# 03_CPU01.net
KiCad netlist of a schematic drawn in Altium Designer
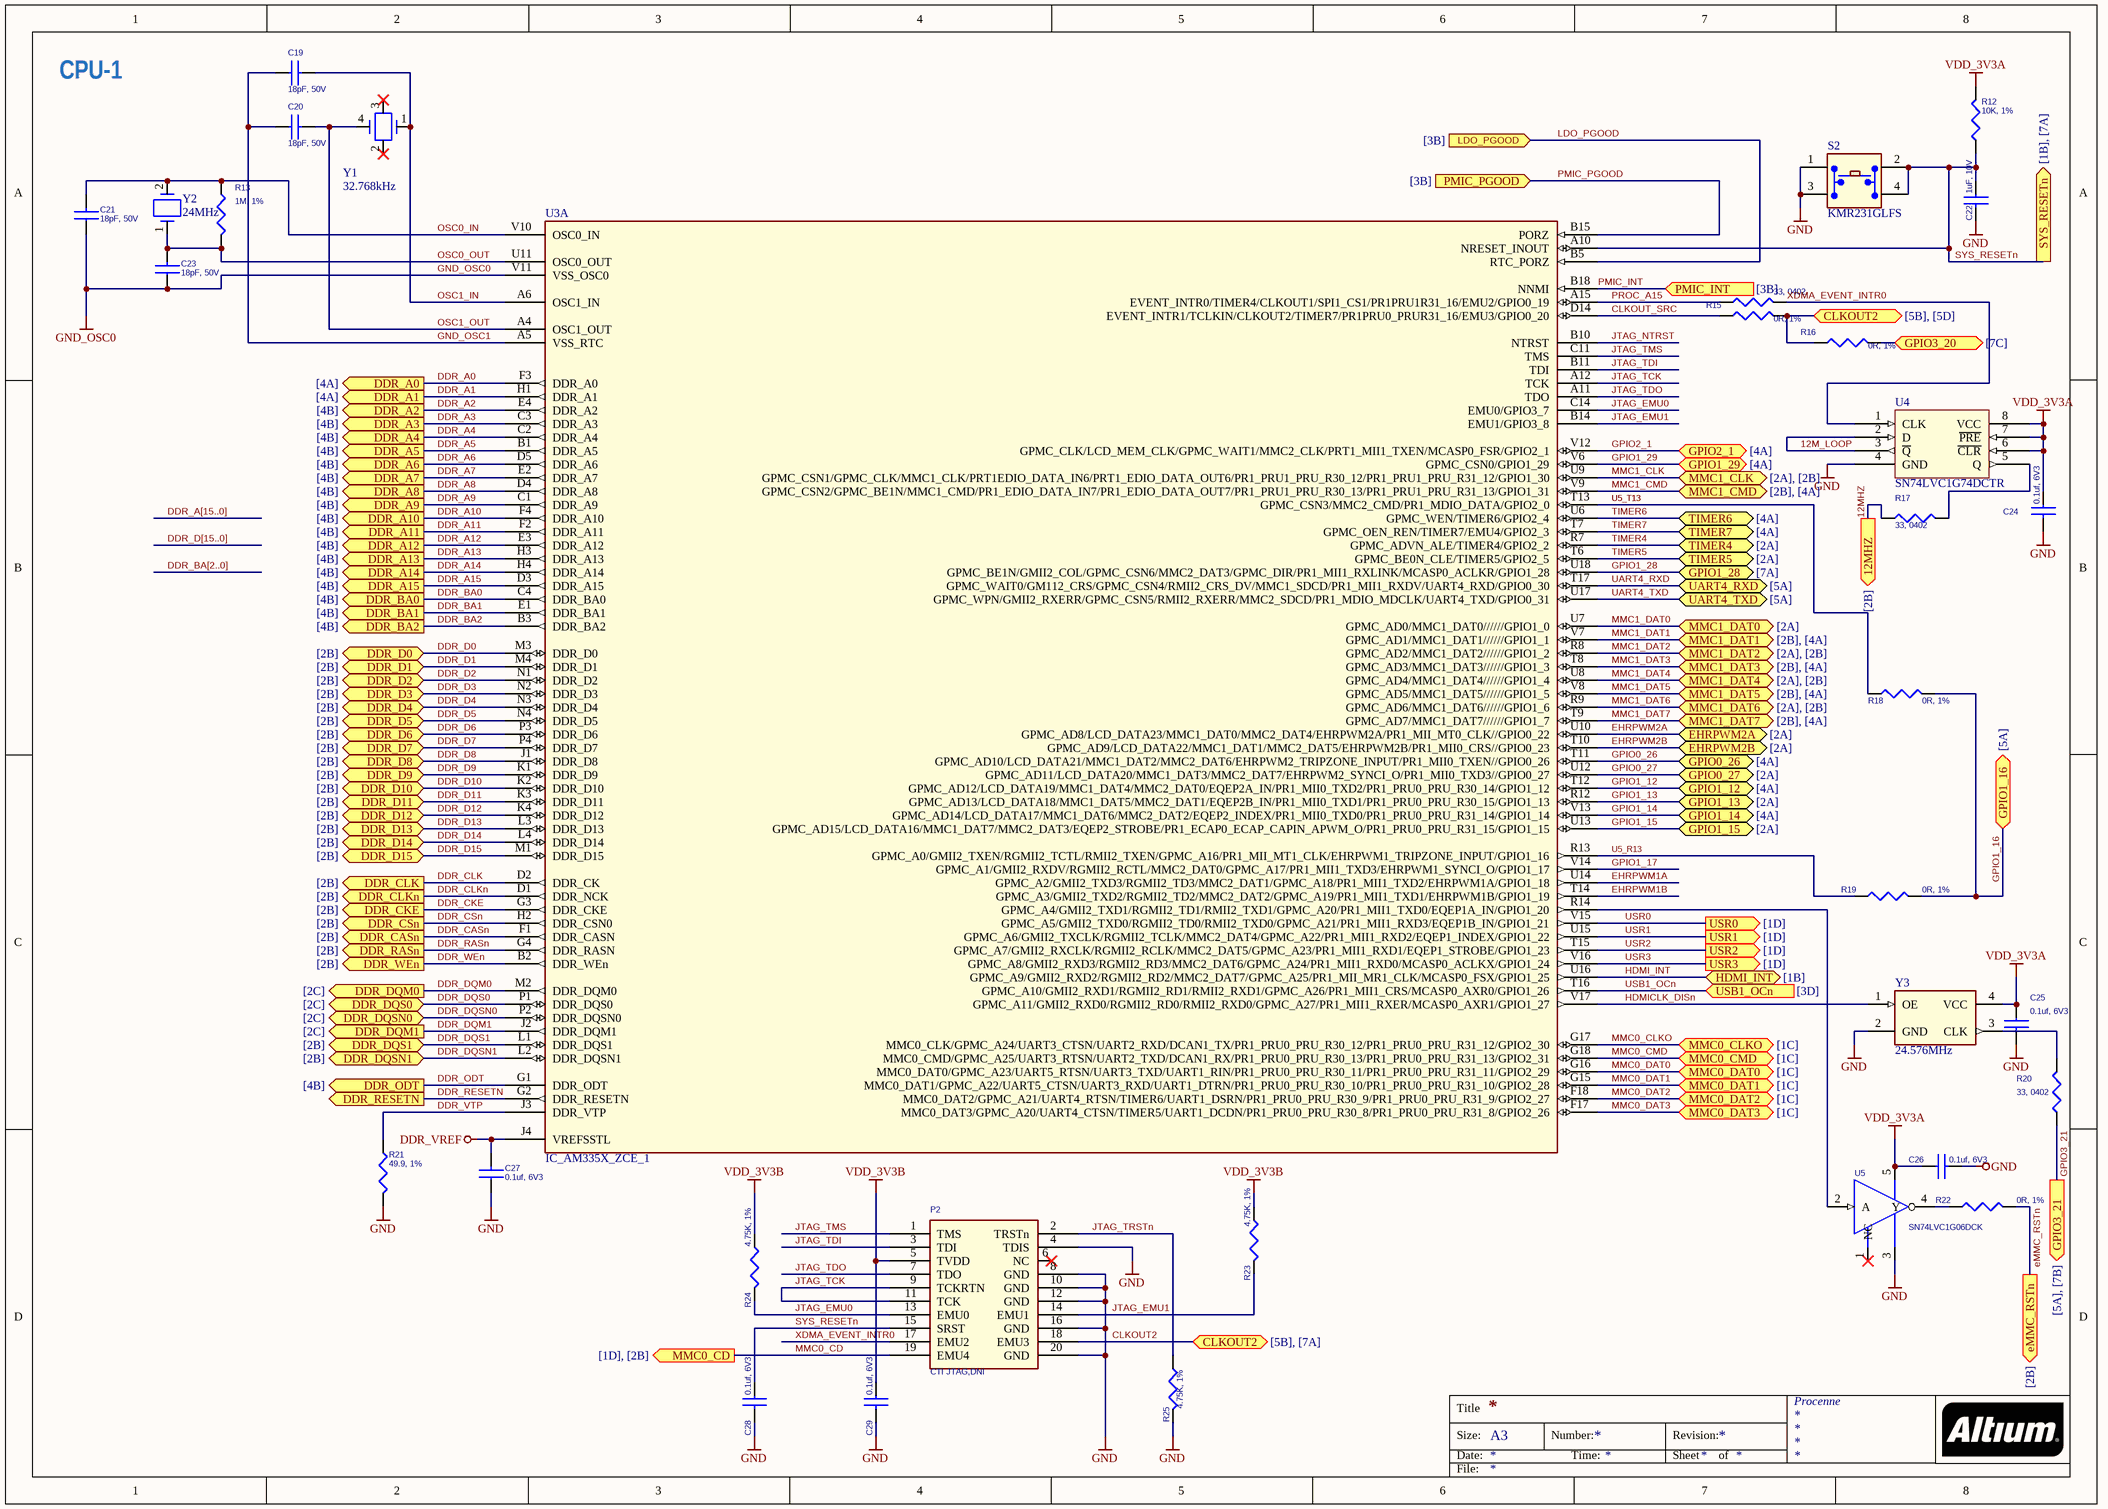
[diagram p0: 03_CPU01.SchDoc]

(export (version "E")
  (design (tool "Eeschema 10.0.6"))
  (components
    (comp (ref "C19")
      (value "18pF, 50V")
      (footprint "402")
      (description "CAP CER 18PF 50V 5% NP0 0402")
      (fields
        (field (name "MANUFACTURER") "TDK Corporation")
        (field (name "MANUFACTURER PART NUMBER") "C1005C0G1H180J050BA")
      )
      (libsource (lib "BEAGLEBONEBLACK_REV A5B") (part "CAP_18PF_COG_50V_5%_0402"))
    )
    (comp (ref "C20")
      (value "18pF, 50V")
      (footprint "402")
      (description "CAP CER 18PF 50V 5% NP0 0402")
      (fields
        (field (name "MANUFACTURER") "TDK Corporation")
        (field (name "MANUFACTURER PART NUMBER") "C1005C0G1H180J050BA")
      )
      (libsource (lib "BEAGLEBONEBLACK_REV A5B") (part "CAP_18PF_COG_50V_5%_0402"))
    )
    (comp (ref "C21")
      (value "18pF, 50V")
      (footprint "402")
      (description "CAP CER 18PF 50V 5% NP0 0402")
      (fields
        (field (name "MANUFACTURER") "TDK Corporation")
        (field (name "MANUFACTURER PART NUMBER") "C1005C0G1H180J050BA")
      )
      (libsource (lib "BEAGLEBONEBLACK_REV A5B_1") (part "CAP_18PF_COG_50V_5%_0402"))
    )
    (comp (ref "C22")
      (value "1uF, 10V")
      (footprint "402")
      (description "CAP CER 1UF 10V 10% X5R 0402")
      (fields
        (field (name "MANUFACTURER") "AVX Corporation")
        (field (name "MANUFACTURER PART NUMBER") "0402ZD105KAT2A")
      )
      (libsource (lib "BEAGLEBONEBLACK_REV A5B") (part "CAP_1.0UF_X5R_10V_10%_0402"))
    )
    (comp (ref "C23")
      (value "18pF, 50V")
      (footprint "402")
      (description "CAP CER 18PF 50V 5% NP0 0402")
      (fields
        (field (name "MANUFACTURER") "TDK Corporation")
        (field (name "MANUFACTURER PART NUMBER") "C1005C0G1H180J050BA")
      )
      (libsource (lib "BEAGLEBONEBLACK_REV A5B_1") (part "CAP_18PF_COG_50V_5%_0402"))
    )
    (comp (ref "C24")
      (value "0.1uf, 6V3")
      (footprint "402")
      (description "CAP CER 0.1UF 6.3V 10% X5R 0402")
      (fields
        (field (name "MANUFACTURER") "TDK Corporation")
        (field (name "MANUFACTURER PART NUMBER") "C1005X5R0J104K050BA")
      )
      (libsource (lib "BEAGLEBONEBLACK_REV A5B") (part "CAP_0.1uF_X7R_16V_10% 0402"))
    )
    (comp (ref "C25")
      (value "0.1uf, 6V3")
      (footprint "402")
      (description "CAP CER 0.1UF 6.3V 10% X5R 0402")
      (fields
        (field (name "MANUFACTURER") "TDK Corporation")
        (field (name "MANUFACTURER PART NUMBER") "C1005X5R0J104K050BA")
      )
      (libsource (lib "BEAGLEBONEBLACK_REV A5B") (part "CAP_0.1uF_X7R_16V_10% 0402"))
    )
    (comp (ref "C26")
      (value "0.1uf, 6V3")
      (footprint "402")
      (description "CAP CER 0.1UF 6.3V 10% X5R 0402")
      (fields
        (field (name "MANUFACTURER") "TDK Corporation")
        (field (name "MANUFACTURER PART NUMBER") "C1005X5R0J104K050BA")
      )
      (libsource (lib "BEAGLEBONEBLACK_REV A5B") (part "CAP_0.1uF_X7R_16V_10% 0402"))
    )
    (comp (ref "C27")
      (value "0.1uf, 6V3")
      (footprint "402")
      (description "CAP CER 0.1UF 6.3V 10% X5R 0402")
      (fields
        (field (name "MANUFACTURER") "TDK Corporation")
        (field (name "MANUFACTURER PART NUMBER") "C1005X5R0J104K050BA")
      )
      (libsource (lib "BEAGLEBONEBLACK_REV A5B_1") (part "CAP_0.1uF_X7R_16V_10% 0402"))
    )
    (comp (ref "C28")
      (value "0.1uf, 6V3")
      (footprint "402")
      (description "CAP CER 0.1UF 6.3V 10% X5R 0402")
      (fields
        (field (name "MANUFACTURER") "TDK Corporation")
        (field (name "MANUFACTURER PART NUMBER") "C1005X5R0J104K050BA")
      )
      (libsource (lib "BEAGLEBONEBLACK_REV A5B") (part "CAP_0.1uF_X7R_16V_10% 0402"))
    )
    (comp (ref "C29")
      (value "0.1uf, 6V3")
      (footprint "402")
      (description "CAP CER 0.1UF 6.3V 10% X5R 0402")
      (fields
        (field (name "MANUFACTURER") "TDK Corporation")
        (field (name "MANUFACTURER PART NUMBER") "C1005X5R0J104K050BA")
      )
      (libsource (lib "BEAGLEBONEBLACK_REV A5B") (part "CAP_0.1uF_X7R_16V_10% 0402"))
    )
    (comp (ref "P2")
      (value "CTI JTAG,DNI")
      (description "Dual Line Header 10x2pin Tin")
      (fields
        (field (name "MANUFACTURER") "Samtec Inc")
        (field (name "MANUFACTURER PART NUMBER") "FTR-110-03-G-D-06")
      )
      (libsource (lib "BEAGLEBONEBLACK_REV A5B") (part "HDR_10x2_CJTAG"))
    )
    (comp (ref "R12")
      (value "10K, 1%")
      (footprint "402")
      (description "RES 10K OHM 1/16W 5% 0402 SMD")
      (fields
        (field (name "MANUFACTURER") "Rohm Semiconductor")
        (field (name "MANUFACTURER PART NUMBER") "MCR01MZPJ103")
      )
      (libsource (lib "BEAGLEBONEBLACK_REV A5B_1") (part "RES_10K_1/16W_1%_0402"))
    )
    (comp (ref "R13")
      (value "1M, 1%")
      (footprint "402")
      (description "Resistor 1Mohm 1/16W 1% 0402")
      (fields
        (field (name "MANUFACTURER") "Stackpole Electronics Inc")
        (field (name "MANUFACTURER PART NUMBER") "RMCF0402FT1M00")
      )
      (libsource (lib "BEAGLEBONEBLACK_REV A5B_1") (part "RES_1M_1/16W_1%_0402"))
    )
    (comp (ref "R14")
      (value "33, 0402")
      (footprint "402")
      (description "RES 33 OHM 1/16W 5% 0402 SMD")
      (fields
        (field (name "MANUFACTURER") "Panasonic Electronic Components")
        (field (name "MANUFACTURER PART NUMBER") "ERJ-2GEJ330X")
      )
      (libsource (lib "BEAGLEBONEBLACK_REV A5B") (part "RES_33_0402"))
    )
    (comp (ref "R15")
      (value "0R, 1%")
      (footprint "402")
      (description "RES 0.0 OHM 1/16W 0402 SMD")
      (fields
        (field (name "MANUFACTURER") "Yageo")
        (field (name "MANUFACTURER PART NUMBER") "RC0402JR-070RL")
      )
      (libsource (lib "BEAGLEBONEBLACK_REV A5B") (part "RES_0_1/16W_1%_0402"))
    )
    (comp (ref "R16")
      (value "0R, 1%")
      (footprint "402")
      (description "RES 0.0 OHM 1/16W 0402 SMD")
      (fields
        (field (name "MANUFACTURER") "Yageo")
        (field (name "MANUFACTURER PART NUMBER") "RC0402JR-070RL")
      )
      (libsource (lib "BEAGLEBONEBLACK_REV A5B") (part "RES_0_1/16W_1%_0402"))
    )
    (comp (ref "R17")
      (value "33, 0402")
      (footprint "402")
      (description "RES 33 OHM 1/16W 5% 0402 SMD")
      (fields
        (field (name "MANUFACTURER") "Panasonic Electronic Components")
        (field (name "MANUFACTURER PART NUMBER") "ERJ-2GEJ330X")
      )
      (libsource (lib "BEAGLEBONEBLACK_REV A5B") (part "RES_33_0402"))
    )
    (comp (ref "R18")
      (value "0R, 1%")
      (footprint "402")
      (description "RES 0.0 OHM 1/16W 0402 SMD")
      (fields
        (field (name "MANUFACTURER") "Yageo")
        (field (name "MANUFACTURER PART NUMBER") "RC0402JR-070RL")
      )
      (libsource (lib "BEAGLEBONEBLACK_REV A5B") (part "RES_0_1/16W_1%_0402"))
    )
    (comp (ref "R19")
      (value "0R, 1%")
      (footprint "402")
      (description "RES 0.0 OHM 1/16W 0402 SMD")
      (fields
        (field (name "MANUFACTURER") "Yageo")
        (field (name "MANUFACTURER PART NUMBER") "RC0402JR-070RL")
      )
      (libsource (lib "BEAGLEBONEBLACK_REV A5B") (part "RES_0_1/16W_1%_0402"))
    )
    (comp (ref "R20")
      (value "33, 0402")
      (footprint "402")
      (description "RES 33 OHM 1/16W 5% 0402 SMD")
      (fields
        (field (name "MANUFACTURER") "Panasonic Electronic Components")
        (field (name "MANUFACTURER PART NUMBER") "ERJ-2GEJ330X")
      )
      (libsource (lib "BEAGLEBONEBLACK_REV A5B") (part "RES_33_0402"))
    )
    (comp (ref "R21")
      (value "49.9, 1%")
      (footprint "402")
      (description "RES 49.9 OHM 1/16W 1% 0402 SMD")
      (fields
        (field (name "MANUFACTURER") "Yageo")
        (field (name "MANUFACTURER PART NUMBER") "RC0402FR-0749R9L")
      )
      (libsource (lib "BEAGLEBONEBLACK_REV A5B_1") (part "RES_4.7K_0402"))
    )
    (comp (ref "R22")
      (value "0R, 1%")
      (footprint "402")
      (description "RES 0.0 OHM 1/16W 0402 SMD")
      (fields
        (field (name "MANUFACTURER") "Yageo")
        (field (name "MANUFACTURER PART NUMBER") "RC0402JR-070RL")
      )
      (libsource (lib "BEAGLEBONEBLACK_REV A5B") (part "RES_0_1/16W_1%_0402"))
    )
    (comp (ref "R23")
      (value "4.75K, 1%")
      (footprint "402")
      (description "RES 4.75K 1/16W 1% 0402 SMD")
      (fields
        (field (name "MANUFACTURER") "Stackpole Electronics Inc")
        (field (name "MANUFACTURER PART NUMBER") "RMCF0402FT4K75")
      )
      (libsource (lib "BEAGLEBONEBLACK_REV A5B") (part "RES_4.7K_0402"))
    )
    (comp (ref "R24")
      (value "4.75K, 1%")
      (footprint "402")
      (description "RES 4.75K 1/16W 1% 0402 SMD")
      (fields
        (field (name "MANUFACTURER") "Stackpole Electronics Inc")
        (field (name "MANUFACTURER PART NUMBER") "RMCF0402FT4K75")
      )
      (libsource (lib "BEAGLEBONEBLACK_REV A5B") (part "RES_4.7K_0402"))
    )
    (comp (ref "R25")
      (value "4.75K, 1%")
      (footprint "402")
      (description "RES 4.75K 1/16W 1% 0402 SMD")
      (fields
        (field (name "MANUFACTURER") "Stackpole Electronics Inc")
        (field (name "MANUFACTURER PART NUMBER") "RMCF0402FT4K75")
      )
      (libsource (lib "BEAGLEBONEBLACK_REV A5B") (part "RES_4.7K_0402"))
    )
    (comp (ref "S2")
      (value "KMR231GLFS")
      (footprint "SW4SMD_63X161LS")
      (description "Microminiature Tact Switch for SMT")
      (fields (field (name "MANUFACTURER") "C&K Components"))
      (libsource (lib "BEAGLEBONEBLACK_REV A5B") (part "KMR2"))
    )
    (comp (ref "U3")
      (value "IC_AM335X_ZCE_1")
      (footprint "am33xx_15x15")
      (description "SubArctic Cortex A8 Processor 15x15")
      (fields
        (field (name "MANUFACTURER") "Texas Instruments")
        (field (name "MANUFACTURER PART NUMBER") "XAM3359ZCZ")
      )
      (libsource (lib "BEAGLEBONEBLACK_REV A5B_1") (part "IC_AM335X_ZCE_1"))
    )
    (comp (ref "U4")
      (value "SN74LVC1G74DCTR")
      (footprint "SOP8_DCT")
      (description "SINGLE  POSITIVE-EDGE-TRIGGERED  D-TYPE  FLIP-FLOP WITH  CLEAR  AND  PRESET")
      (fields (field (name "MANUFACTURER") "Texas Instruments"))
      (libsource (lib "BEAGLEBONEBLACK_REV A5B") (part "SN74LVC1G74DCTR"))
    )
    (comp (ref "U5")
      (value "SN74LVC1G06DCK")
      (footprint "DCK5_2P15X1P4")
      (description "IC INVERTER SINGLE 1INPUT SC705")
      (fields
        (field (name "MANUFACTURER") "Texas Instruments")
        (field (name "MANUFACTURER PART NUMBER") "SN74LVC1G06DCKTG4")
      )
      (libsource (lib "BEAGLEBONEBLACK_REV A5B") (part "SN74LVC1G06DCK"))
    )
    (comp (ref "Y1")
      (value "32.768kHz")
      (footprint "XTAL4_126-216SMD")
      (description "CRYSTAL 32.768KHZ 12.5PF SMD")
      (fields
        (field (name "MANUFACTURER") "Citizen Finetech Miyota")
        (field (name "MANUFACTURER PART NUMBER") "CM200C-32.768KAZF-UT")
      )
      (libsource (lib "BEAGLEBONEBLACK_REV A5B_1") (part "CRYS_32_768KHz_SMD32"))
    )
    (comp (ref "Y2")
      (value "24MHz")
      (footprint "XTAL150SMD_125X196")
      (description "CRYSTAL 24.000MHZ 18PF SMD")
      (fields
        (field (name "MANUFACTURER") "TXC CORPORATION")
        (field (name "MANUFACTURER PART NUMBER") "7A-24.000MAAJ-T")
      )
      (libsource (lib "BEAGLEBONEBLACK_REV A5B_1") (part "CRYS_24MHz_SCC"))
    )
    (comp (ref "Y3")
      (value "24.576MHz")
      (footprint "OSC4_61X65LS_79X98SMD")
      (fields
        (field (name "MANUFACTURER") "Abracon Corporation")
        (field (name "MANUFACTURER PART NUMBER") "ASDMB-24.576MHZ-LC-T")
      )
      (libsource (lib "BEAGLEBONEBLACK_REV A5B") (part "ASDMB"))
    )
  )
  (nets
    (net (code "1") (name "/12MHZ") (class "Default")
      (node (ref "R17") (pin "1") (pinfunction "1_1") (pintype "passive"))
    )
    (net (code "2") (name "/12M_LOOP") (class "Default")
      (node (ref "U4") (pin "2") (pinfunction "D_2") (pintype "input"))
      (node (ref "U4") (pin "3") (pinfunction "~{Q}_3") (pintype "output"))
    )
    (net (code "3") (name "/CLKOUT2") (class "Default")
      (node (ref "P2") (pin "18") (pinfunction "EMU3_18") (pintype "passive"))
      (node (ref "R15") (pin "2") (pinfunction "2_2") (pintype "passive"))
      (node (ref "R16") (pin "1") (pinfunction "1_1") (pintype "passive"))
    )
    (net (code "4") (name "/CLKOUT_SRC") (class "Default")
      (node (ref "R15") (pin "1") (pinfunction "1_1") (pintype "passive"))
      (node (ref "U3") (pin "D14") (pinfunction "EVENT_INTR1/TCLKIN/CLKOUT2/TIMER7/PR1PRU0_PRUR31_16/EMU3/GPIO0_20_D14") (pintype "bidirectional"))
    )
    (net (code "5") (name "/DDR_A0") (class "Default")
      (node (ref "U3") (pin "F3") (pinfunction "DDR_A0_F3") (pintype "output"))
    )
    (net (code "6") (name "/DDR_A1") (class "Default")
      (node (ref "U3") (pin "H1") (pinfunction "DDR_A1_H1") (pintype "output"))
    )
    (net (code "7") (name "/DDR_A2") (class "Default")
      (node (ref "U3") (pin "E4") (pinfunction "DDR_A2_E4") (pintype "output"))
    )
    (net (code "8") (name "/DDR_A3") (class "Default")
      (node (ref "U3") (pin "C3") (pinfunction "DDR_A3_C3") (pintype "output"))
    )
    (net (code "9") (name "/DDR_A4") (class "Default")
      (node (ref "U3") (pin "C2") (pinfunction "DDR_A4_C2") (pintype "output"))
    )
    (net (code "10") (name "/DDR_A5") (class "Default")
      (node (ref "U3") (pin "B1") (pinfunction "DDR_A5_B1") (pintype "output"))
    )
    (net (code "11") (name "/DDR_A6") (class "Default")
      (node (ref "U3") (pin "D5") (pinfunction "DDR_A6_D5") (pintype "output"))
    )
    (net (code "12") (name "/DDR_A7") (class "Default")
      (node (ref "U3") (pin "E2") (pinfunction "DDR_A7_E2") (pintype "output"))
    )
    (net (code "13") (name "/DDR_A8") (class "Default")
      (node (ref "U3") (pin "D4") (pinfunction "DDR_A8_D4") (pintype "output"))
    )
    (net (code "14") (name "/DDR_A9") (class "Default")
      (node (ref "U3") (pin "C1") (pinfunction "DDR_A9_C1") (pintype "output"))
    )
    (net (code "15") (name "/DDR_A10") (class "Default")
      (node (ref "U3") (pin "F4") (pinfunction "DDR_A10_F4") (pintype "output"))
    )
    (net (code "16") (name "/DDR_A11") (class "Default")
      (node (ref "U3") (pin "F2") (pinfunction "DDR_A11_F2") (pintype "output"))
    )
    (net (code "17") (name "/DDR_A12") (class "Default")
      (node (ref "U3") (pin "E3") (pinfunction "DDR_A12_E3") (pintype "output"))
    )
    (net (code "18") (name "/DDR_A13") (class "Default")
      (node (ref "U3") (pin "H3") (pinfunction "DDR_A13_H3") (pintype "output"))
    )
    (net (code "19") (name "/DDR_A14") (class "Default")
      (node (ref "U3") (pin "H4") (pinfunction "DDR_A14_H4") (pintype "output"))
    )
    (net (code "20") (name "/DDR_A15") (class "Default")
      (node (ref "U3") (pin "D3") (pinfunction "DDR_A15_D3") (pintype "output"))
    )
    (net (code "22") (name "/DDR_BA0") (class "Default")
      (node (ref "U3") (pin "C4") (pinfunction "DDR_BA0_C4") (pintype "output"))
    )
    (net (code "23") (name "/DDR_BA1") (class "Default")
      (node (ref "U3") (pin "E1") (pinfunction "DDR_BA1_E1") (pintype "output"))
    )
    (net (code "24") (name "/DDR_BA2") (class "Default")
      (node (ref "U3") (pin "B3") (pinfunction "DDR_BA2_B3") (pintype "output"))
    )
    (net (code "26") (name "/DDR_CASn") (class "Default")
      (node (ref "U3") (pin "F1") (pinfunction "DDR_CASN_F1") (pintype "output"))
    )
    (net (code "27") (name "/DDR_CKE") (class "Default")
      (node (ref "U3") (pin "G3") (pinfunction "DDR_CKE_G3") (pintype "output"))
    )
    (net (code "28") (name "/DDR_CLK") (class "Default")
      (node (ref "U3") (pin "D2") (pinfunction "DDR_CK_D2") (pintype "output"))
    )
    (net (code "29") (name "/DDR_CLKn") (class "Default")
      (node (ref "U3") (pin "D1") (pinfunction "DDR_NCK_D1") (pintype "output"))
    )
    (net (code "30") (name "/DDR_CSn") (class "Default")
      (node (ref "U3") (pin "H2") (pinfunction "DDR_CSN0_H2") (pintype "output"))
    )
    (net (code "31") (name "/DDR_D0") (class "Default")
      (node (ref "U3") (pin "M3") (pinfunction "DDR_D0_M3") (pintype "bidirectional"))
    )
    (net (code "32") (name "/DDR_D1") (class "Default")
      (node (ref "U3") (pin "M4") (pinfunction "DDR_D1_M4") (pintype "bidirectional"))
    )
    (net (code "33") (name "/DDR_D2") (class "Default")
      (node (ref "U3") (pin "N1") (pinfunction "DDR_D2_N1") (pintype "bidirectional"))
    )
    (net (code "34") (name "/DDR_D3") (class "Default")
      (node (ref "U3") (pin "N2") (pinfunction "DDR_D3_N2") (pintype "bidirectional"))
    )
    (net (code "35") (name "/DDR_D4") (class "Default")
      (node (ref "U3") (pin "N3") (pinfunction "DDR_D4_N3") (pintype "bidirectional"))
    )
    (net (code "36") (name "/DDR_D5") (class "Default")
      (node (ref "U3") (pin "N4") (pinfunction "DDR_D5_N4") (pintype "bidirectional"))
    )
    (net (code "37") (name "/DDR_D6") (class "Default")
      (node (ref "U3") (pin "P3") (pinfunction "DDR_D6_P3") (pintype "bidirectional"))
    )
    (net (code "38") (name "/DDR_D7") (class "Default")
      (node (ref "U3") (pin "P4") (pinfunction "DDR_D7_P4") (pintype "bidirectional"))
    )
    (net (code "39") (name "/DDR_D8") (class "Default")
      (node (ref "U3") (pin "J1") (pinfunction "DDR_D8_J1") (pintype "bidirectional"))
    )
    (net (code "40") (name "/DDR_D9") (class "Default")
      (node (ref "U3") (pin "K1") (pinfunction "DDR_D9_K1") (pintype "bidirectional"))
    )
    (net (code "41") (name "/DDR_D10") (class "Default")
      (node (ref "U3") (pin "K2") (pinfunction "DDR_D10_K2") (pintype "bidirectional"))
    )
    (net (code "42") (name "/DDR_D11") (class "Default")
      (node (ref "U3") (pin "K3") (pinfunction "DDR_D11_K3") (pintype "bidirectional"))
    )
    (net (code "43") (name "/DDR_D12") (class "Default")
      (node (ref "U3") (pin "K4") (pinfunction "DDR_D12_K4") (pintype "bidirectional"))
    )
    (net (code "44") (name "/DDR_D13") (class "Default")
      (node (ref "U3") (pin "L3") (pinfunction "DDR_D13_L3") (pintype "bidirectional"))
    )
    (net (code "45") (name "/DDR_D14") (class "Default")
      (node (ref "U3") (pin "L4") (pinfunction "DDR_D14_L4") (pintype "bidirectional"))
    )
    (net (code "46") (name "/DDR_D15") (class "Default")
      (node (ref "U3") (pin "M1") (pinfunction "DDR_D15_M1") (pintype "bidirectional"))
    )
    (net (code "47") (name "/DDR_DQM0") (class "Default")
      (node (ref "U3") (pin "M2") (pinfunction "DDR_DQM0_M2") (pintype "output"))
    )
    (net (code "48") (name "/DDR_DQM1") (class "Default")
      (node (ref "U3") (pin "J2") (pinfunction "DDR_DQM1_J2") (pintype "output"))
    )
    (net (code "49") (name "/DDR_DQS0") (class "Default")
      (node (ref "U3") (pin "P1") (pinfunction "DDR_DQS0_P1") (pintype "bidirectional"))
    )
    (net (code "50") (name "/DDR_DQS1") (class "Default")
      (node (ref "U3") (pin "L1") (pinfunction "DDR_DQS1_L1") (pintype "bidirectional"))
    )
    (net (code "51") (name "/DDR_DQSN0") (class "Default")
      (node (ref "U3") (pin "P2") (pinfunction "DDR_DQSN0_P2") (pintype "bidirectional"))
    )
    (net (code "52") (name "/DDR_DQSN1") (class "Default")
      (node (ref "U3") (pin "L2") (pinfunction "DDR_DQSN1_L2") (pintype "bidirectional"))
    )
    (net (code "54") (name "/DDR_ODT") (class "Default")
      (node (ref "U3") (pin "G1") (pinfunction "DDR_ODT_G1") (pintype "passive"))
    )
    (net (code "55") (name "/DDR_RASn") (class "Default")
      (node (ref "U3") (pin "G4") (pinfunction "DDR_RASN_G4") (pintype "output"))
    )
    (net (code "56") (name "/DDR_RESETN") (class "Default")
      (node (ref "U3") (pin "G2") (pinfunction "DDR_RESETN_G2") (pintype "output"))
    )
    (net (code "57") (name "/DDR_VTP") (class "Default")
      (node (ref "R21") (pin "1") (pinfunction "1_1") (pintype "passive"))
      (node (ref "U3") (pin "J3") (pinfunction "DDR_VTP_J3") (pintype "passive"))
    )
    (net (code "58") (name "/DDR_WEn") (class "Default")
      (node (ref "U3") (pin "B2") (pinfunction "DDR_WEn_B2") (pintype "output"))
    )
    (net (code "59") (name "/EHRPWM1A") (class "Default")
      (node (ref "U3") (pin "U14") (pinfunction "GPMC_A2/GMII2_TXD3/RGMII2_TD3/MMC2_DAT1/GPMC_A18/PR1_MII1_TXD2/EHRPWM1A/GPIO1_18_U14") (pintype "output"))
    )
    (net (code "60") (name "/EHRPWM1B") (class "Default")
      (node (ref "U3") (pin "T14") (pinfunction "GPMC_A3/GMII2_TXD2/RGMII2_TD2/MMC2_DAT2/GPMC_A19/PR1_MII1_TXD1/EHRPWM1B/GPIO1_19_T14") (pintype "output"))
    )
    (net (code "61") (name "/EHRPWM2A") (class "Default")
      (node (ref "U3") (pin "U10") (pinfunction "GPMC_AD8/LCD_DATA23/MMC1_DAT0/MMC2_DAT4/EHRPWM2A/PR1_MII_MT0_CLK//GPIO0_22_U10") (pintype "bidirectional"))
    )
    (net (code "62") (name "/EHRPWM2B") (class "Default")
      (node (ref "U3") (pin "T10") (pinfunction "GPMC_AD9/LCD_DATA22/MMC1_DAT1/MMC2_DAT5/EHRPWM2B/PR1_MII0_CRS//GPIO0_23_T10") (pintype "bidirectional"))
    )
    (net (code "63") (name "/GND_OSC1") (class "Default")
      (node (ref "C19") (pin "1") (pinfunction "1_1") (pintype "passive"))
      (node (ref "C20") (pin "1") (pinfunction "1_1") (pintype "passive"))
      (node (ref "U3") (pin "A5") (pinfunction "VSS_RTC_A5") (pintype "power_in"))
    )
    (net (code "64") (name "/GPIO0_26") (class "Default")
      (node (ref "U3") (pin "T11") (pinfunction "GPMC_AD10/LCD_DATA21/MMC1_DAT2/MMC2_DAT6/EHRPWM2_TRIPZONE_INPUT/PR1_MII0_TXEN//GPIO0_26_T11") (pintype "bidirectional"))
    )
    (net (code "65") (name "/GPIO0_27") (class "Default")
      (node (ref "U3") (pin "U12") (pinfunction "GPMC_AD11/LCD_DATA20/MMC1_DAT3/MMC2_DAT7/EHRPWM2_SYNCI_O/PR1_MII0_TXD3//GPIO0_27_U12") (pintype "bidirectional"))
    )
    (net (code "66") (name "/GPIO1_12") (class "Default")
      (node (ref "U3") (pin "T12") (pinfunction "GPMC_AD12/LCD_DATA19/MMC1_DAT4/MMC2_DAT0/EQEP2A_IN/PR1_MII0_TXD2/PR1_PRU0_PRU_R30_14/GPIO1_12_T12") (pintype "bidirectional"))
    )
    (net (code "67") (name "/GPIO1_13") (class "Default")
      (node (ref "U3") (pin "R12") (pinfunction "GPMC_AD13/LCD_DATA18/MMC1_DAT5/MMC2_DAT1/EQEP2B_IN/PR1_MII0_TXD1/PR1_PRU0_PRU_R30_15/GPIO1_13_R12") (pintype "bidirectional"))
    )
    (net (code "68") (name "/GPIO1_14") (class "Default")
      (node (ref "U3") (pin "V13") (pinfunction "GPMC_AD14/LCD_DATA17/MMC1_DAT6/MMC2_DAT2/EQEP2_INDEX/PR1_MII0_TXD0/PR1_PRU0_PRU_R31_14/GPIO1_14_V13") (pintype "bidirectional"))
    )
    (net (code "69") (name "/GPIO1_15") (class "Default")
      (node (ref "U3") (pin "U13") (pinfunction "GPMC_AD15/LCD_DATA16/MMC1_DAT7/MMC2_DAT3/EQEP2_STROBE/PR1_ECAP0_ECAP_CAPIN_APWM_O/PR1_PRU0_PRU_R31_15/GPIO1_15_U13") (pintype "bidirectional"))
    )
    (net (code "70") (name "/GPIO1_16") (class "Default")
      (node (ref "R18") (pin "2") (pinfunction "2_2") (pintype "passive"))
      (node (ref "R19") (pin "2") (pinfunction "2_2") (pintype "passive"))
    )
    (net (code "71") (name "/GPIO1_17") (class "Default")
      (node (ref "U3") (pin "V14") (pinfunction "GPMC_A1/GMII2_RXDV/RGMII2_RCTL/MMC2_DAT0/GPMC_A17/PR1_MII1_TXD3/EHRPWM1_SYNCI_O/GPIO1_17_V14") (pintype "output"))
    )
    (net (code "72") (name "/GPIO1_28") (class "Default")
      (node (ref "U3") (pin "U18") (pinfunction "GPMC_BE1N/GMII2_COL/GPMC_CSN6/MMC2_DAT3/GPMC_DIR/PR1_MII1_RXLINK/MCASP0_ACLKR/GPIO1_28_U18") (pintype "bidirectional"))
    )
    (net (code "73") (name "/GPIO1_29") (class "Default")
      (node (ref "U3") (pin "V6") (pinfunction "GPMC_CSN0/GPIO1_29_V6") (pintype "bidirectional"))
    )
    (net (code "74") (name "/GPIO2_1") (class "Default")
      (node (ref "U3") (pin "V12") (pinfunction "GPMC_CLK/LCD_MEM_CLK/GPMC_WAIT1/MMC2_CLK/PRT1_MII1_TXEN/MCASP0_FSR/GPIO2_1_V12") (pintype "bidirectional"))
    )
    (net (code "75") (name "/GPIO3_20") (class "Default")
      (node (ref "R16") (pin "2") (pinfunction "2_2") (pintype "passive"))
    )
    (net (code "76") (name "/GPIO3_21") (class "Default")
      (node (ref "R20") (pin "1") (pinfunction "1_1") (pintype "passive"))
    )
    (net (code "77") (name "/HDMICLK_DISn") (class "Default")
      (node (ref "U3") (pin "V17") (pinfunction "GPMC_A11/GMII2_RXD0/RGMII2_RD0/RMII2_RXD0/GPMC_A27/PR1_MII1_RXER/MCASP0_AXR1/GPIO1_27_V17") (pintype "output"))
      (node (ref "Y3") (pin "1") (pinfunction "OE_1") (pintype "input"))
    )
    (net (code "78") (name "/HDMI_INT") (class "Default")
      (node (ref "U3") (pin "U16") (pinfunction "GPMC_A9/GMII2_RXD2/RGMII2_RD2/MMC2_DAT7/GPMC_A25/PR1_MII_MR1_CLK/MCASP0_FSX/GPIO1_25_U16") (pintype "output"))
    )
    (net (code "79") (name "/JTAG_EMU0") (class "Default")
      (node (ref "P2") (pin "13") (pinfunction "EMU0_13") (pintype "passive"))
      (node (ref "R24") (pin "2") (pinfunction "2_2") (pintype "passive"))
      (node (ref "U3") (pin "C14") (pinfunction "EMU0/GPIO3_7_C14") (pintype "passive"))
    )
    (net (code "80") (name "/JTAG_EMU1") (class "Default")
      (node (ref "P2") (pin "14") (pinfunction "EMU1_14") (pintype "passive"))
      (node (ref "R23") (pin "2") (pinfunction "2_2") (pintype "passive"))
      (node (ref "U3") (pin "B14") (pinfunction "EMU1/GPIO3_8_B14") (pintype "passive"))
    )
    (net (code "81") (name "/JTAG_NTRST") (class "Default")
      (node (ref "U3") (pin "B10") (pinfunction "NTRST_B10") (pintype "passive"))
    )
    (net (code "82") (name "/JTAG_TCK") (class "Default")
      (node (ref "P2") (pin "11") (pinfunction "TCK_11") (pintype "passive"))
      (node (ref "P2") (pin "9") (pinfunction "TCKRTN_9") (pintype "passive"))
      (node (ref "U3") (pin "A12") (pinfunction "TCK_A12") (pintype "passive"))
    )
    (net (code "83") (name "/JTAG_TDI") (class "Default")
      (node (ref "P2") (pin "3") (pinfunction "TDI_3") (pintype "passive"))
      (node (ref "U3") (pin "B11") (pinfunction "TDI_B11") (pintype "passive"))
    )
    (net (code "84") (name "/JTAG_TDO") (class "Default")
      (node (ref "P2") (pin "7") (pinfunction "TDO_7") (pintype "passive"))
      (node (ref "U3") (pin "A11") (pinfunction "TDO_A11") (pintype "passive"))
    )
    (net (code "85") (name "/JTAG_TMS") (class "Default")
      (node (ref "P2") (pin "1") (pinfunction "TMS_1") (pintype "passive"))
      (node (ref "U3") (pin "C11") (pinfunction "TMS_C11") (pintype "passive"))
    )
    (net (code "86") (name "/JTAG_TRSTn") (class "Default")
      (node (ref "P2") (pin "2") (pinfunction "TRSTn_2") (pintype "passive"))
      (node (ref "R25") (pin "1") (pinfunction "1_1") (pintype "passive"))
    )
    (net (code "87") (name "/LDO_PGOOD") (class "Default")
      (node (ref "U3") (pin "B5") (pinfunction "RTC_PORZ_B5") (pintype "input"))
    )
    (net (code "88") (name "/MMC0_CD") (class "Default")
      (node (ref "P2") (pin "19") (pinfunction "EMU4_19") (pintype "passive"))
    )
    (net (code "89") (name "/MMC0_CLKO") (class "Default")
      (node (ref "U3") (pin "G17") (pinfunction "MMC0_CLK/GPMC_A24/UART3_CTSN/UART2_RXD/DCAN1_TX/PR1_PRU0_PRU_R30_12/PR1_PRU0_PRU_R31_12/GPIO2_30_G17") (pintype "bidirectional"))
    )
    (net (code "90") (name "/MMC0_CMD") (class "Default")
      (node (ref "U3") (pin "G18") (pinfunction "MMC0_CMD/GPMC_A25/UART3_RTSN/UART2_TXD/DCAN1_RX/PR1_PRU0_PRU_R30_13/PR1_PRU0_PRU_R31_13/GPIO2_31_G18") (pintype "bidirectional"))
    )
    (net (code "91") (name "/MMC0_DAT0") (class "Default")
      (node (ref "U3") (pin "G16") (pinfunction "MMC0_DAT0/GPMC_A23/UART5_RTSN/UART3_TXD/UART1_RIN/PR1_PRU0_PRU_R30_11/PR1_PRU0_PRU_R31_11/GPIO2_29_G16") (pintype "bidirectional"))
    )
    (net (code "92") (name "/MMC0_DAT1") (class "Default")
      (node (ref "U3") (pin "G15") (pinfunction "MMC0_DAT1/GPMC_A22/UART5_CTSN/UART3_RXD/UART1_DTRN/PR1_PRU0_PRU_R30_10/PR1_PRU0_PRU_R31_10/GPIO2_28_G15") (pintype "bidirectional"))
    )
    (net (code "93") (name "/MMC0_DAT2") (class "Default")
      (node (ref "U3") (pin "F18") (pinfunction "MMC0_DAT2/GPMC_A21/UART4_RTSN/TIMER6/UART1_DSRN/PR1_PRU0_PRU_R30_9/PR1_PRU0_PRU_R31_9/GPIO2_27_F18") (pintype "bidirectional"))
    )
    (net (code "94") (name "/MMC0_DAT3") (class "Default")
      (node (ref "U3") (pin "F17") (pinfunction "MMC0_DAT3/GPMC_A20/UART4_CTSN/TIMER5/UART1_DCDN/PR1_PRU0_PRU_R30_8/PR1_PRU0_PRU_R31_8/GPIO2_26_F17") (pintype "bidirectional"))
    )
    (net (code "95") (name "/MMC1_CLK") (class "Default")
      (node (ref "U3") (pin "U9") (pinfunction "GPMC_CSN1/GPMC_CLK/MMC1_CLK/PRT1EDIO_DATA_IN6/PRT1_EDIO_DATA_OUT6/PR1_PRU1_PRU_R30_12/PR1_PRU1_PRU_R31_12/GPIO1_30_U9") (pintype "bidirectional"))
    )
    (net (code "96") (name "/MMC1_CMD") (class "Default")
      (node (ref "U3") (pin "V9") (pinfunction "GPMC_CSN2/GPMC_BE1N/MMC1_CMD/PR1_EDIO_DATA_IN7/PR1_EDIO_DATA_OUT7/PR1_PRU1_PRU_R30_13/PR1_PRU1_PRU_R31_13/GPIO1_31_V9") (pintype "bidirectional"))
    )
    (net (code "97") (name "/MMC1_DAT0") (class "Default")
      (node (ref "U3") (pin "U7") (pinfunction "GPMC_AD0/MMC1_DAT0//////GPIO1_0_U7") (pintype "bidirectional"))
    )
    (net (code "98") (name "/MMC1_DAT1") (class "Default")
      (node (ref "U3") (pin "V7") (pinfunction "GPMC_AD1/MMC1_DAT1//////GPIO1_1_V7") (pintype "bidirectional"))
    )
    (net (code "99") (name "/MMC1_DAT2") (class "Default")
      (node (ref "U3") (pin "R8") (pinfunction "GPMC_AD2/MMC1_DAT2//////GPIO1_2_R8") (pintype "bidirectional"))
    )
    (net (code "100") (name "/MMC1_DAT3") (class "Default")
      (node (ref "U3") (pin "T8") (pinfunction "GPMC_AD3/MMC1_DAT3//////GPIO1_3_T8") (pintype "bidirectional"))
    )
    (net (code "101") (name "/MMC1_DAT4") (class "Default")
      (node (ref "U3") (pin "U8") (pinfunction "GPMC_AD4/MMC1_DAT4//////GPIO1_4_U8") (pintype "bidirectional"))
    )
    (net (code "102") (name "/MMC1_DAT5") (class "Default")
      (node (ref "U3") (pin "V8") (pinfunction "GPMC_AD5/MMC1_DAT5//////GPIO1_5_V8") (pintype "bidirectional"))
    )
    (net (code "103") (name "/MMC1_DAT6") (class "Default")
      (node (ref "U3") (pin "R9") (pinfunction "GPMC_AD6/MMC1_DAT6//////GPIO1_6_R9") (pintype "bidirectional"))
    )
    (net (code "104") (name "/MMC1_DAT7") (class "Default")
      (node (ref "U3") (pin "T9") (pinfunction "GPMC_AD7/MMC1_DAT7//////GPIO1_7_T9") (pintype "bidirectional"))
    )
    (net (code "105") (name "/OSC0_IN") (class "Default")
      (node (ref "C21") (pin "2") (pinfunction "2_2") (pintype "passive"))
      (node (ref "R13") (pin "1") (pinfunction "1_1") (pintype "passive"))
      (node (ref "U3") (pin "V10") (pinfunction "OSC0_IN_V10") (pintype "passive"))
      (node (ref "Y2") (pin "2") (pinfunction "2_2") (pintype "passive"))
    )
    (net (code "106") (name "/OSC0_OUT") (class "Default")
      (node (ref "C23") (pin "2") (pinfunction "2_2") (pintype "passive"))
      (node (ref "R13") (pin "2") (pinfunction "2_2") (pintype "passive"))
      (node (ref "U3") (pin "U11") (pinfunction "OSC0_OUT_U11") (pintype "passive"))
      (node (ref "Y2") (pin "1") (pinfunction "1_1") (pintype "passive"))
    )
    (net (code "107") (name "/OSC1_IN") (class "Default")
      (node (ref "C19") (pin "2") (pinfunction "2_2") (pintype "passive"))
      (node (ref "U3") (pin "A6") (pinfunction "OSC1_IN_A6") (pintype "passive"))
      (node (ref "Y1") (pin "1") (pinfunction "1_1") (pintype "passive"))
    )
    (net (code "108") (name "/OSC1_OUT") (class "Default")
      (node (ref "C20") (pin "2") (pinfunction "2_2") (pintype "passive"))
      (node (ref "U3") (pin "A4") (pinfunction "OSC1_OUT_A4") (pintype "passive"))
      (node (ref "Y1") (pin "4") (pinfunction "4_4") (pintype "passive"))
    )
    (net (code "109") (name "/PMIC_INT") (class "Default")
      (node (ref "U3") (pin "B18") (pinfunction "NNMI_B18") (pintype "input"))
    )
    (net (code "110") (name "/PMIC_PGOOD") (class "Default")
      (node (ref "U3") (pin "B15") (pinfunction "PORZ_B15") (pintype "input"))
    )
    (net (code "111") (name "/PROC_A15") (class "Default")
      (node (ref "R14") (pin "1") (pinfunction "1_1") (pintype "passive"))
      (node (ref "U3") (pin "A15") (pinfunction "EVENT_INTR0/TIMER4/CLKOUT1/SPI1_CS1/PR1PRU1R31_16/EMU2/GPIO0_19_A15") (pintype "bidirectional"))
    )
    (net (code "112") (name "/SYS_RESETn") (class "Default")
      (node (ref "C22") (pin "1") (pinfunction "1_1") (pintype "passive"))
      (node (ref "C28") (pin "1") (pinfunction "1_1") (pintype "passive"))
      (node (ref "P2") (pin "15") (pinfunction "SRST_15") (pintype "passive"))
      (node (ref "R12") (pin "1") (pinfunction "1_1") (pintype "passive"))
      (node (ref "S2") (pin "2") (pinfunction "A2_2") (pintype "passive"))
      (node (ref "S2") (pin "4") (pinfunction "4_4") (pintype "power_in"))
      (node (ref "U3") (pin "A10") (pinfunction "NRESET_INOUT_A10") (pintype "bidirectional"))
    )
    (net (code "113") (name "/TIMER4") (class "Default")
      (node (ref "U3") (pin "R7") (pinfunction "GPMC_ADVN_ALE/TIMER4/GPIO2_2_R7") (pintype "bidirectional"))
    )
    (net (code "114") (name "/TIMER5") (class "Default")
      (node (ref "U3") (pin "T6") (pinfunction "GPMC_BE0N_CLE/TIMER5/GPIO2_5_T6") (pintype "bidirectional"))
    )
    (net (code "115") (name "/TIMER6") (class "Default")
      (node (ref "U3") (pin "U6") (pinfunction "GPMC_WEN/TIMER6/GPIO2_4_U6") (pintype "bidirectional"))
    )
    (net (code "116") (name "/TIMER7") (class "Default")
      (node (ref "U3") (pin "T7") (pinfunction "GPMC_OEN_REN/TIMER7/EMU4/GPIO2_3_T7") (pintype "bidirectional"))
    )
    (net (code "117") (name "/U5_R13") (class "Default")
      (node (ref "R19") (pin "1") (pinfunction "1_1") (pintype "passive"))
      (node (ref "U3") (pin "R13") (pinfunction "GPMC_A0/GMII2_TXEN/RGMII2_TCTL/RMII2_TXEN/GPMC_A16/PR1_MII_MT1_CLK/EHRPWM1_TRIPZONE_INPUT/GPIO1_16_R13") (pintype "output"))
    )
    (net (code "118") (name "/U5_T13") (class "Default")
      (node (ref "R18") (pin "1") (pinfunction "1_1") (pintype "passive"))
      (node (ref "U3") (pin "T13") (pinfunction "GPMC_CSN3/MMC2_CMD/PR1_MDIO_DATA/GPIO2_0_T13") (pintype "bidirectional"))
    )
    (net (code "119") (name "/UART4_RXD") (class "Default")
      (node (ref "U3") (pin "T17") (pinfunction "GPMC_WAIT0/GM112_CRS/GPMC_CSN4/RMII2_CRS_DV/MMC1_SDCD/PR1_MII1_RXDV/UART4_RXD/GPIO0_30_T17") (pintype "bidirectional"))
    )
    (net (code "120") (name "/UART4_TXD") (class "Default")
      (node (ref "U3") (pin "U17") (pinfunction "GPMC_WPN/GMII2_RXERR/GPMC_CSN5/RMII2_RXERR/MMC2_SDCD/PR1_MDIO_MDCLK/UART4_TXD/GPIO0_31_U17") (pintype "bidirectional"))
    )
    (net (code "121") (name "/USB1_OCn") (class "Default")
      (node (ref "U3") (pin "T16") (pinfunction "GPMC_A10/GMII2_RXD1/RGMII2_RD1/RMII2_RXD1/GPMC_A26/PR1_MII1_CRS/MCASP0_AXR0/GPIO1_26_T16") (pintype "output"))
    )
    (net (code "122") (name "/USR0") (class "Default")
      (node (ref "U3") (pin "V15") (pinfunction "GPMC_A5/GMII2_TXD0/RGMII2_TD0/RMII2_TXD0/GPMC_A21/PR1_MII1_RXD3/EQEP1B_IN/GPIO1_21_V15") (pintype "output"))
    )
    (net (code "123") (name "/USR1") (class "Default")
      (node (ref "U3") (pin "U15") (pinfunction "GPMC_A6/GMII2_TXCLK/RGMII2_TCLK/MMC2_DAT4/GPMC_A22/PR1_MII1_RXD2/EQEP1_INDEX/GPIO1_22_U15") (pintype "output"))
    )
    (net (code "124") (name "/USR2") (class "Default")
      (node (ref "U3") (pin "T15") (pinfunction "GPMC_A7/GMII2_RXCLK/RGMII2_RCLK/MMC2_DAT5/GPMC_A23/PR1_MII1_RXD1/EQEP1_STROBE/GPIO1_23_T15") (pintype "output"))
    )
    (net (code "125") (name "/USR3") (class "Default")
      (node (ref "U3") (pin "V16") (pinfunction "GPMC_A8/GMII2_RXD3/RGMII2_RD3/MMC2_DAT6/GPMC_A24/PR1_MII1_RXD0/MCASP0_ACLKX/GPIO1_24_V16") (pintype "output"))
    )
    (net (code "126") (name "/XDMA_EVENT_INTR0") (class "Default")
      (node (ref "P2") (pin "17") (pinfunction "EMU2_17") (pintype "passive"))
      (node (ref "R14") (pin "2") (pinfunction "2_2") (pintype "passive"))
      (node (ref "U4") (pin "1") (pinfunction "CLK_1") (pintype "input"))
    )
    (net (code "127") (name "/eMMC_RSTn") (class "Default")
      (node (ref "R22") (pin "2") (pinfunction "2_2") (pintype "passive"))
    )
    (net (code "128") (name "DDR_VREF") (class "Default")
      (node (ref "C27") (pin "2") (pinfunction "2_2") (pintype "passive"))
      (node (ref "U3") (pin "J4") (pinfunction "VREFSSTL_J4") (pintype "passive"))
    )
    (net (code "129") (name "GND") (class "Default")
      (node (ref "C22") (pin "2") (pinfunction "2_2") (pintype "passive"))
      (node (ref "C24") (pin "2") (pinfunction "2_2") (pintype "passive"))
      (node (ref "C25") (pin "2") (pinfunction "2_2") (pintype "passive"))
      (node (ref "C26") (pin "2") (pinfunction "2_2") (pintype "passive"))
      (node (ref "C27") (pin "1") (pinfunction "1_1") (pintype "passive"))
      (node (ref "C28") (pin "2") (pinfunction "2_2") (pintype "passive"))
      (node (ref "C29") (pin "2") (pinfunction "2_2") (pintype "passive"))
      (node (ref "P2") (pin "10") (pinfunction "GND_10") (pintype "power_in"))
      (node (ref "P2") (pin "12") (pinfunction "GND_12") (pintype "power_in"))
      (node (ref "P2") (pin "16") (pinfunction "GND_16") (pintype "power_in"))
      (node (ref "P2") (pin "20") (pinfunction "GND_20") (pintype "power_in"))
      (node (ref "P2") (pin "4") (pinfunction "TDIS_4") (pintype "passive"))
      (node (ref "P2") (pin "8") (pinfunction "GND_8") (pintype "power_in"))
      (node (ref "R21") (pin "2") (pinfunction "2_2") (pintype "passive"))
      (node (ref "R25") (pin "2") (pinfunction "2_2") (pintype "passive"))
      (node (ref "S2") (pin "1") (pinfunction "A1_1") (pintype "passive"))
      (node (ref "S2") (pin "3") (pinfunction "A3_3") (pintype "passive"))
      (node (ref "U4") (pin "4") (pinfunction "GND_4") (pintype "power_in"))
      (node (ref "U5") (pin "3") (pinfunction "GND_3") (pintype "power_in"))
      (node (ref "Y3") (pin "2") (pinfunction "GND_2") (pintype "power_in"))
    )
    (net (code "130") (name "GND_OSC0") (class "Default")
      (node (ref "C21") (pin "1") (pinfunction "1_1") (pintype "passive"))
      (node (ref "C23") (pin "1") (pinfunction "1_1") (pintype "passive"))
      (node (ref "U3") (pin "V11") (pinfunction "VSS_OSC0_V11") (pintype "power_in"))
    )
    (net (code "131") (name "Net-(U3A-GPMC_A4{slash}GMII2_TXD1{slash}RGMII2_TD1{slash}RMII2_TXD1{slash}GPMC_A20{slash}PR1_MII1_TXD0{slash}EQEP1A_IN{slash}GPIO1_20)") (class "Default")
      (node (ref "U3") (pin "R14") (pinfunction "GPMC_A4/GMII2_TXD1/RGMII2_TD1/RMII2_TXD1/GPMC_A20/PR1_MII1_TXD0/EQEP1A_IN/GPIO1_20_R14") (pintype "output"))
      (node (ref "U5") (pin "2") (pinfunction "A_2") (pintype "input"))
    )
    (net (code "132") (name "Net-(U4-Q)") (class "Default")
      (node (ref "R17") (pin "2") (pinfunction "2_2") (pintype "passive"))
      (node (ref "U4") (pin "5") (pinfunction "Q_5") (pintype "output"))
    )
    (net (code "133") (name "Net-(U5-Y)") (class "Default")
      (node (ref "R22") (pin "1") (pinfunction "1_1") (pintype "passive"))
      (node (ref "U5") (pin "4") (pinfunction "Y_4") (pintype "open_collector"))
    )
    (net (code "134") (name "Net-(Y3-CLK)") (class "Default")
      (node (ref "R20") (pin "2") (pinfunction "2_2") (pintype "passive"))
      (node (ref "Y3") (pin "3") (pinfunction "CLK_3") (pintype "output"))
    )
    (net (code "135") (name "VDD_3V3A") (class "Default")
      (node (ref "C24") (pin "1") (pinfunction "1_1") (pintype "passive"))
      (node (ref "C25") (pin "1") (pinfunction "1_1") (pintype "passive"))
      (node (ref "C26") (pin "1") (pinfunction "1_1") (pintype "passive"))
      (node (ref "R12") (pin "2") (pinfunction "2_2") (pintype "passive"))
      (node (ref "U4") (pin "6") (pinfunction "~{CLR}_6") (pintype "input"))
      (node (ref "U4") (pin "7") (pinfunction "~{PRE}_7") (pintype "input"))
      (node (ref "U4") (pin "8") (pinfunction "VCC_8") (pintype "power_in"))
      (node (ref "U5") (pin "5") (pinfunction "VCC_5") (pintype "power_in"))
      (node (ref "Y3") (pin "4") (pinfunction "VCC_4") (pintype "power_in"))
    )
    (net (code "136") (name "VDD_3V3B") (class "Default")
      (node (ref "C29") (pin "1") (pinfunction "1_1") (pintype "passive"))
      (node (ref "P2") (pin "5") (pinfunction "TVDD_5") (pintype "passive"))
      (node (ref "R23") (pin "1") (pinfunction "1_1") (pintype "passive"))
      (node (ref "R24") (pin "1") (pinfunction "1_1") (pintype "passive"))
    )
    (net (code "137") (name "unconnected-(P2-NC-Pad6)") (class "Default")
      (node (ref "P2") (pin "6") (pinfunction "NC_6") (pintype "passive+no_connect"))
    )
    (net (code "138") (name "unconnected-(U5-NC-Pad1)") (class "Default")
      (node (ref "U5") (pin "1") (pinfunction "NC_1") (pintype "passive+no_connect"))
    )
    (net (code "139") (name "unconnected-(Y1-Pad2)") (class "Default")
      (node (ref "Y1") (pin "2") (pinfunction "2_2") (pintype "passive+no_connect"))
    )
    (net (code "140") (name "unconnected-(Y1-Pad3)") (class "Default")
      (node (ref "Y1") (pin "3") (pinfunction "3_3") (pintype "passive+no_connect"))
    )
  )
)
